# 14-I225-Main.net
KiCad netlist of a schematic drawn in Altium Designer
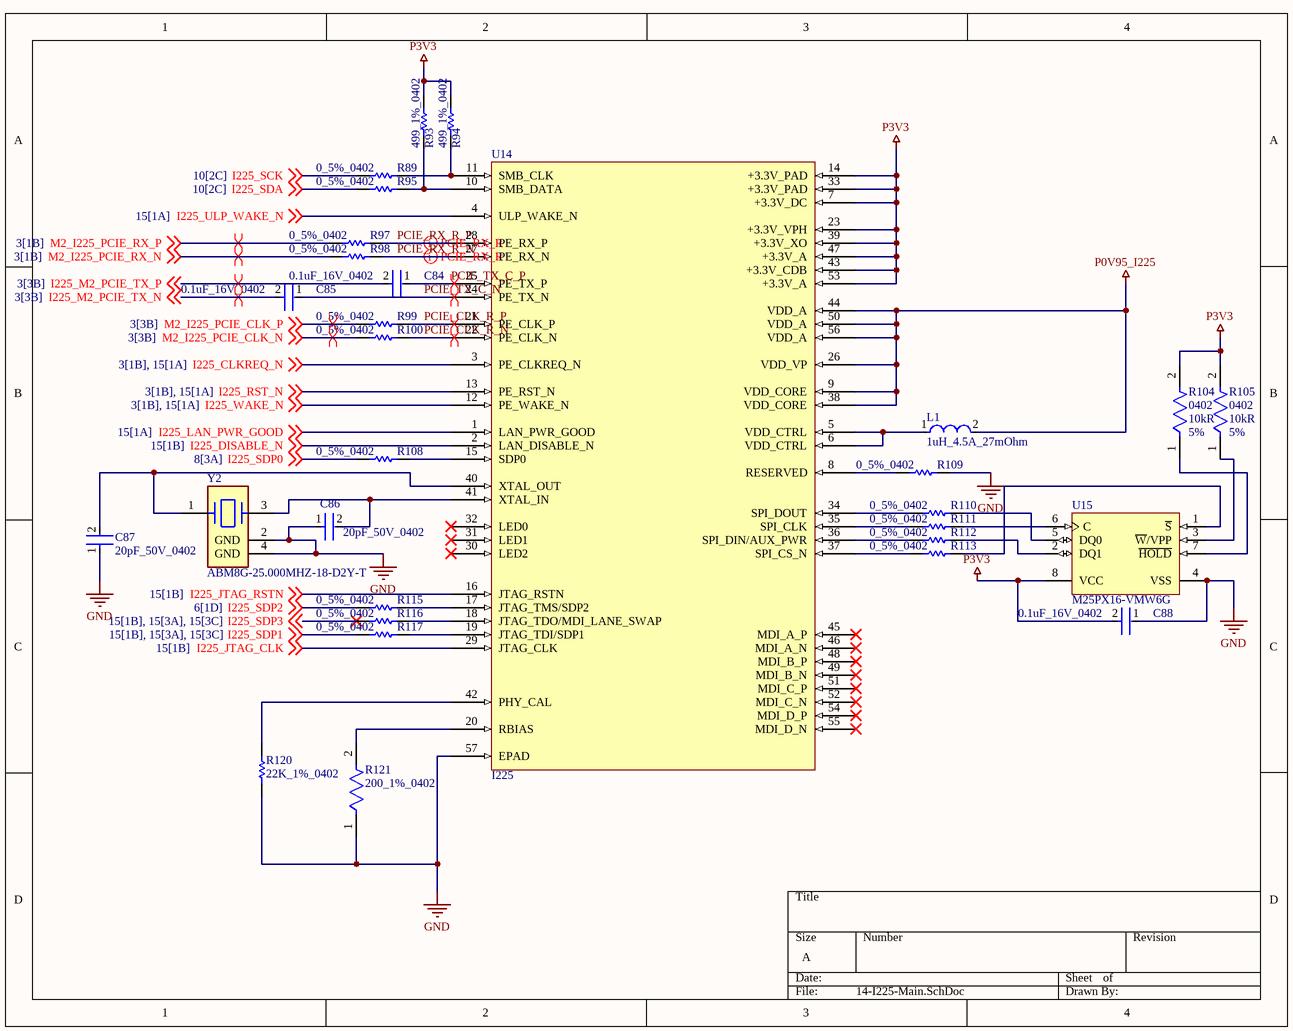
[diagram p0: 14-I225-Main.SchDoc]

(export (version "E")
  (design (tool "Eeschema 10.0.6"))
  (components
    (comp (ref "C84")
      (value "0.1uF_16V_0402")
      (footprint "FP-GRM15-MFG")
      (description "CAP CER 0.1UF 16V X7R 0402")
      (fields (field (name "MANUFACTURER PART NUMBER") "GRM155R71C104KA88D") (field (name "TOLERANCE") "10%"))
      (libsource (lib "Altium Content Vault") (part "236180d848d6139a670b325ea6854c9"))
    )
    (comp (ref "C85")
      (value "0.1uF_16V_0402")
      (footprint "FP-GRM15-MFG")
      (description "CAP CER 0.1UF 16V X7R 0402")
      (fields (field (name "MANUFACTURER PART NUMBER") "GRM155R71C104KA88D") (field (name "TOLERANCE") "10%"))
      (libsource (lib "Altium Content Vault") (part "236180d848d6139a670b325ea6854c9"))
    )
    (comp (ref "C86")
      (value "20pF_50V_0402")
      (footprint "FP-C0402-BB-MFG")
      (description "CAP CER 20PF 50V 5% NP0 0402")
      (fields
        (field (name "MANUFACTURER PART NUMBER") "C0402C200J5GACTU")
        (field (name "OCTOPART") "https://octopart.com/c0402c200j5gactu-kemet-9143900")
      )
      (libsource (lib "Altium Content Vault") (part "b4654b650e69147ec39a6b967a45e02"))
    )
    (comp (ref "C87")
      (value "20pF_50V_0402")
      (footprint "FP-C0402-BB-MFG")
      (description "CAP CER 20PF 50V 5% NP0 0402")
      (fields
        (field (name "MANUFACTURER PART NUMBER") "C0402C200J5GACTU")
        (field (name "OCTOPART") "https://octopart.com/c0402c200j5gactu-kemet-9143900")
      )
      (libsource (lib "Altium Content Vault") (part "b4654b650e69147ec39a6b967a45e02"))
    )
    (comp (ref "C88")
      (value "0.1uF_16V_0402")
      (footprint "FP-GRM15-MFG")
      (description "CAP CER 0.1UF 16V X7R 0402")
      (fields (field (name "MANUFACTURER PART NUMBER") "GRM155R71C104KA88D") (field (name "TOLERANCE") "10%"))
      (libsource (lib "Altium Content Vault") (part "236180d848d6139a670b325ea6854c9"))
    )
    (comp (ref "L1")
      (value "1uH_4.5A_27mOhm")
      (footprint "FP-IHLP-1616BZ-FP_1_8545x-MFG")
      (description "Fixed Inductors Commercial Low DCR Series SMT 1uH 4.5A 27mΩ 20%")
      (fields (field (name "TOLERANCE") "20%"))
      (libsource (lib "Altium Content Vault") (part "725321dda6339637d4d059423bc1c3c"))
    )
    (comp (ref "R89")
      (value "0_5%_0402")
      (footprint "RESC1005X40X25LL10T10")
      (fields (field (name "MANUFACTURER") "KOA Speer") (field (name "PART NUMBER") "RK73Z1ETTP"))
      (libsource (lib "Altium Content Vault") (part "RES"))
    )
    (comp (ref "R93")
      (value "499_1%_0402")
      (footprint "RESC1005X40X25LL05T05")
      (fields (field (name "MANUFACTURER") "Panasonic") (field (name "PART NUMBER") "ERJ-2RKF4990X"))
      (libsource (lib "Altium Content Vault") (part "RES"))
    )
    (comp (ref "R94")
      (value "499_1%_0402")
      (footprint "RESC1005X40X25LL05T05")
      (fields (field (name "MANUFACTURER") "Panasonic") (field (name "PART NUMBER") "ERJ-2RKF4990X"))
      (libsource (lib "Altium Content Vault") (part "RES"))
    )
    (comp (ref "R95")
      (value "0_5%_0402")
      (footprint "RESC1005X40X25LL10T10")
      (fields (field (name "MANUFACTURER") "KOA Speer") (field (name "PART NUMBER") "RK73Z1ETTP"))
      (libsource (lib "Altium Content Vault") (part "RES"))
    )
    (comp (ref "R97")
      (value "0_5%_0402")
      (footprint "RESC1005X40X25LL10T10")
      (fields (field (name "MANUFACTURER") "KOA Speer") (field (name "PART NUMBER") "RK73Z1ETTP"))
      (libsource (lib "Altium Content Vault") (part "RES"))
    )
    (comp (ref "R98")
      (value "0_5%_0402")
      (footprint "RESC1005X40X25LL10T10")
      (fields (field (name "MANUFACTURER") "KOA Speer") (field (name "PART NUMBER") "RK73Z1ETTP"))
      (libsource (lib "Altium Content Vault") (part "RES"))
    )
    (comp (ref "R99")
      (value "0_5%_0402")
      (footprint "RESC1005X40X25LL10T10")
      (fields (field (name "MANUFACTURER") "KOA Speer") (field (name "PART NUMBER") "RK73Z1ETTP"))
      (libsource (lib "Altium Content Vault") (part "RES"))
    )
    (comp (ref "R100")
      (value "0_5%_0402")
      (footprint "RESC1005X40X25LL10T10")
      (fields (field (name "MANUFACTURER") "KOA Speer") (field (name "PART NUMBER") "RK73Z1ETTP"))
      (libsource (lib "Altium Content Vault") (part "RES"))
    )
    (comp (ref "R104")
      (value "CRCW040210K0JNED")
      (footprint "FP-CRCW0402-e3-IPC_B")
      (description "RES Thick Film, 10kΩ, 5%, 0.063W, 200ppm/°C, 0402")
      (fields
        (field (name "CASE/PACKAGE") "0402")
        (field (name "RESISTANCE") "10kR")
        (field (name "TOLERANCE") "5%")
      )
      (libsource (lib "Altium Content Vault") (part "1029c3af85768c4190bb7ad29bc67b5"))
    )
    (comp (ref "R105")
      (value "CRCW040210K0JNED")
      (footprint "FP-CRCW0402-e3-IPC_B")
      (description "RES Thick Film, 10kΩ, 5%, 0.063W, 200ppm/°C, 0402")
      (fields
        (field (name "CASE/PACKAGE") "0402")
        (field (name "RESISTANCE") "10kR")
        (field (name "TOLERANCE") "5%")
      )
      (libsource (lib "Altium Content Vault") (part "1029c3af85768c4190bb7ad29bc67b5"))
    )
    (comp (ref "R108")
      (value "0_5%_0402")
      (footprint "RESC1005X40X25LL10T10")
      (fields (field (name "MANUFACTURER") "KOA Speer") (field (name "PART NUMBER") "RK73Z1ETTP"))
      (libsource (lib "Altium Content Vault") (part "RES"))
    )
    (comp (ref "R109")
      (value "0_5%_0402")
      (footprint "RESC1005X40X25LL10T10")
      (fields (field (name "MANUFACTURER") "KOA Speer") (field (name "PART NUMBER") "RK73Z1ETTP"))
      (libsource (lib "Altium Content Vault") (part "RES"))
    )
    (comp (ref "R110")
      (value "0_5%_0402")
      (footprint "RESC1005X40X25LL10T10")
      (fields (field (name "MANUFACTURER") "KOA Speer") (field (name "PART NUMBER") "RK73Z1ETTP"))
      (libsource (lib "Altium Content Vault") (part "RES"))
    )
    (comp (ref "R111")
      (value "0_5%_0402")
      (footprint "RESC1005X40X25LL10T10")
      (fields (field (name "MANUFACTURER") "KOA Speer") (field (name "PART NUMBER") "RK73Z1ETTP"))
      (libsource (lib "Altium Content Vault") (part "RES"))
    )
    (comp (ref "R112")
      (value "0_5%_0402")
      (footprint "RESC1005X40X25LL10T10")
      (fields (field (name "MANUFACTURER") "KOA Speer") (field (name "PART NUMBER") "RK73Z1ETTP"))
      (libsource (lib "Altium Content Vault") (part "RES"))
    )
    (comp (ref "R113")
      (value "0_5%_0402")
      (footprint "RESC1005X40X25LL10T10")
      (fields (field (name "MANUFACTURER") "KOA Speer") (field (name "PART NUMBER") "RK73Z1ETTP"))
      (libsource (lib "Altium Content Vault") (part "RES"))
    )
    (comp (ref "R115")
      (value "0_5%_0402")
      (footprint "RESC1005X40X25LL10T10")
      (fields (field (name "MANUFACTURER") "KOA Speer") (field (name "PART NUMBER") "RK73Z1ETTP"))
      (libsource (lib "Altium Content Vault") (part "RES"))
    )
    (comp (ref "R116")
      (value "0_5%_0402")
      (footprint "RESC1005X40X25LL10T10")
      (fields (field (name "MANUFACTURER") "KOA Speer") (field (name "PART NUMBER") "RK73Z1ETTP"))
      (libsource (lib "Altium Content Vault") (part "RES"))
    )
    (comp (ref "R117")
      (value "0_5%_0402")
      (footprint "RESC1005X40X25LL10T10")
      (fields (field (name "MANUFACTURER") "KOA Speer") (field (name "PART NUMBER") "RK73Z1ETTP"))
      (libsource (lib "Altium Content Vault") (part "RES"))
    )
    (comp (ref "R120")
      (value "22K_1%_0402")
      (footprint "RESC1005X40X25NL05T05")
      (fields (field (name "PART NUMBER") "CRCW040222K0FKED") (field (name "MANUFACTURER") "Vishay Dale"))
      (libsource (lib "Altium Content Vault") (part "RES"))
    )
    (comp (ref "R121")
      (value "200_1%_0402")
      (footprint "FP-CRCW0402-e3-IPC_C")
      (description "RES Thick Film, 200Ω, 1%, 0.063W, 100ppm/°C, 0402")
      (fields (field (name "TOLERANCE") "1%"))
      (libsource (lib "Altium Content Vault") (part "1029c3af85768c4190bb7ad29bc67b5"))
    )
    (comp (ref "U14") (value "I225") (footprint "I225 QFN56") (libsource (lib "TimeStick_Lib") (part "I225")))
    (comp (ref "U15")
      (value "M25PX16-VMW6G")
      (footprint "MICT-MW-8_N")
      (fields (field (name "VOLTAGE") "2.3V-3.6VÂ") (field (name "MANUFACTURER") "Micron"))
      (libsource (lib "Altium Content Vault") (part "MICT-M25PX16-VMW-8"))
    )
    (comp (ref "Y2")
      (value "ABM8G-25.000MHZ-18-D2Y-T")
      (footprint "FP-ABM8G-MFG")
      (description "CRYSTAL 25.0000MHZ 18PF SMD")
      (fields
        (field (name "MANUFACTURER") "Abracon")
        (field (name "OCTOPART") "https://octopart.com/abm8g-25.000mhz-18-d2y-t-abracon-12676602")
      )
      (libsource (lib "Altium Content Vault") (part "82af6c543cb7a88a4cbd02a3a01c293"))
    )
  )
  (nets
    (net (code "1") (name "/PCIE_CLK_R_N") (class "Default")
      (node (ref "R100") (pin "2") (pinfunction "2_2") (pintype "passive"))
      (node (ref "U14") (pin "22") (pinfunction "PE_CLK_N_22") (pintype "input"))
    )
    (net (code "2") (name "/PCIE_CLK_R_P") (class "Default")
      (node (ref "R99") (pin "2") (pinfunction "2_2") (pintype "passive"))
      (node (ref "U14") (pin "21") (pinfunction "PE_CLK_P_21") (pintype "input"))
    )
    (net (code "3") (name "/PCIE_RX_R_N") (class "Default")
      (node (ref "R98") (pin "2") (pinfunction "2_2") (pintype "passive"))
      (node (ref "U14") (pin "27") (pinfunction "PE_RX_N_27") (pintype "input"))
    )
    (net (code "4") (name "/PCIE_RX_R_P") (class "Default")
      (node (ref "R97") (pin "2") (pinfunction "2_2") (pintype "passive"))
      (node (ref "U14") (pin "28") (pinfunction "PE_RX_P_28") (pintype "input"))
    )
    (net (code "5") (name "/PCIE_TX_C_N") (class "Default")
      (node (ref "C85") (pin "1") (pinfunction "1_1") (pintype "passive"))
      (node (ref "U14") (pin "24") (pinfunction "PE_TX_N_24") (pintype "input"))
    )
    (net (code "6") (name "/PCIE_TX_C_P") (class "Default")
      (node (ref "C84") (pin "1") (pinfunction "1_1") (pintype "passive"))
      (node (ref "U14") (pin "25") (pinfunction "PE_TX_P_25") (pintype "input"))
    )
    (net (code "7") (name "GND") (class "Default")
      (node (ref "C86") (pin "1") (pinfunction "1_1") (pintype "passive"))
      (node (ref "C87") (pin "1") (pinfunction "1_1") (pintype "passive"))
      (node (ref "C88") (pin "1") (pinfunction "1_1") (pintype "passive"))
      (node (ref "R109") (pin "2") (pinfunction "2_2") (pintype "passive"))
      (node (ref "R120") (pin "1") (pinfunction "1_1") (pintype "passive"))
      (node (ref "R121") (pin "1") (pinfunction "1_1") (pintype "passive"))
      (node (ref "U14") (pin "57") (pinfunction "EPAD_57") (pintype "input"))
      (node (ref "U15") (pin "4") (pinfunction "VSS_4") (pintype "power_in"))
      (node (ref "Y2") (pin "2") (pinfunction "GND_2") (pintype "power_in"))
      (node (ref "Y2") (pin "4") (pinfunction "GND_4") (pintype "power_in"))
    )
    (net (code "8") (name "I225_CLKREQ_N") (class "Default")
      (node (ref "U14") (pin "3") (pinfunction "PE_CLKREQ_N_3") (pintype "input"))
    )
    (net (code "9") (name "I225_DISABLE_N") (class "Default")
      (node (ref "U14") (pin "2") (pinfunction "LAN_DISABLE_N_2") (pintype "input"))
    )
    (net (code "10") (name "I225_JTAG_CLK") (class "Default")
      (node (ref "U14") (pin "29") (pinfunction "JTAG_CLK_29") (pintype "input"))
    )
    (net (code "11") (name "I225_JTAG_RSTN") (class "Default")
      (node (ref "U14") (pin "16") (pinfunction "JTAG_RSTN_16") (pintype "input"))
    )
    (net (code "12") (name "I225_LAN_PWR_GOOD") (class "Default")
      (node (ref "U14") (pin "1") (pinfunction "LAN_PWR_GOOD_1") (pintype "input"))
    )
    (net (code "13") (name "I225_M2_PCIE_TX_N") (class "Default")
      (node (ref "C85") (pin "2") (pinfunction "2_2") (pintype "passive"))
    )
    (net (code "14") (name "I225_M2_PCIE_TX_P") (class "Default")
      (node (ref "C84") (pin "2") (pinfunction "2_2") (pintype "passive"))
    )
    (net (code "15") (name "I225_RST_N") (class "Default")
      (node (ref "U14") (pin "13") (pinfunction "PE_RST_N_13") (pintype "input"))
    )
    (net (code "16") (name "I225_SCK") (class "Default")
      (node (ref "R89") (pin "1") (pinfunction "1_1") (pintype "passive"))
    )
    (net (code "17") (name "I225_SDA") (class "Default")
      (node (ref "R95") (pin "1") (pinfunction "1_1") (pintype "passive"))
    )
    (net (code "18") (name "I225_SDP0") (class "Default")
      (node (ref "R108") (pin "1") (pinfunction "1_1") (pintype "passive"))
    )
    (net (code "19") (name "I225_SDP1") (class "Default")
      (node (ref "R117") (pin "1") (pinfunction "1_1") (pintype "passive"))
    )
    (net (code "20") (name "I225_SDP2") (class "Default")
      (node (ref "R115") (pin "1") (pinfunction "1_1") (pintype "passive"))
    )
    (net (code "21") (name "I225_SDP3") (class "Default")
      (node (ref "R116") (pin "1") (pinfunction "1_1") (pintype "passive"))
    )
    (net (code "22") (name "I225_ULP_WAKE_N") (class "Default")
      (node (ref "U14") (pin "4") (pinfunction "ULP_WAKE_N_4") (pintype "input"))
    )
    (net (code "23") (name "I225_WAKE_N") (class "Default")
      (node (ref "U14") (pin "12") (pinfunction "PE_WAKE_N_12") (pintype "input"))
    )
    (net (code "24") (name "M2_I225_PCIE_CLK_N") (class "Default")
      (node (ref "R100") (pin "1") (pinfunction "1_1") (pintype "passive"))
    )
    (net (code "25") (name "M2_I225_PCIE_CLK_P") (class "Default")
      (node (ref "R99") (pin "1") (pinfunction "1_1") (pintype "passive"))
    )
    (net (code "26") (name "M2_I225_PCIE_RX_N") (class "Default")
      (node (ref "R98") (pin "1") (pinfunction "1_1") (pintype "passive"))
    )
    (net (code "27") (name "M2_I225_PCIE_RX_P") (class "Default")
      (node (ref "R97") (pin "1") (pinfunction "1_1") (pintype "passive"))
    )
    (net (code "28") (name "Net-(L1-Pad1)") (class "Default")
      (node (ref "L1") (pin "1") (pinfunction "1_1") (pintype "passive"))
      (node (ref "U14") (pin "5") (pinfunction "VDD_CTRL_5") (pintype "input"))
      (node (ref "U14") (pin "6") (pinfunction "VDD_CTRL_6") (pintype "input"))
    )
    (net (code "29") (name "Net-(U14-JTAG_TDI{slash}SDP1)") (class "Default")
      (node (ref "R117") (pin "2") (pinfunction "2_2") (pintype "passive"))
      (node (ref "U14") (pin "19") (pinfunction "JTAG_TDI/SDP1_19") (pintype "input"))
    )
    (net (code "30") (name "Net-(U14-JTAG_TDO{slash}MDI_LANE_SWAP)") (class "Default")
      (node (ref "R116") (pin "2") (pinfunction "2_2") (pintype "passive"))
      (node (ref "U14") (pin "18") (pinfunction "JTAG_TDO/MDI_LANE_SWAP_18") (pintype "input"))
    )
    (net (code "31") (name "Net-(U14-JTAG_TMS{slash}SDP2)") (class "Default")
      (node (ref "R115") (pin "2") (pinfunction "2_2") (pintype "passive"))
      (node (ref "U14") (pin "17") (pinfunction "JTAG_TMS/SDP2_17") (pintype "input"))
    )
    (net (code "32") (name "Net-(U14-PHY_CAL)") (class "Default")
      (node (ref "R120") (pin "2") (pinfunction "2_2") (pintype "passive"))
      (node (ref "U14") (pin "42") (pinfunction "PHY_CAL_42") (pintype "input"))
    )
    (net (code "33") (name "Net-(U14-RBIAS)") (class "Default")
      (node (ref "R121") (pin "2") (pinfunction "2_2") (pintype "passive"))
      (node (ref "U14") (pin "20") (pinfunction "RBIAS_20") (pintype "input"))
    )
    (net (code "34") (name "Net-(U14-RESERVED)") (class "Default")
      (node (ref "R109") (pin "1") (pinfunction "1_1") (pintype "passive"))
      (node (ref "U14") (pin "8") (pinfunction "RESERVED_8") (pintype "input"))
    )
    (net (code "35") (name "Net-(U14-SDP0)") (class "Default")
      (node (ref "R108") (pin "2") (pinfunction "2_2") (pintype "passive"))
      (node (ref "U14") (pin "15") (pinfunction "SDP0_15") (pintype "input"))
    )
    (net (code "36") (name "Net-(U14-SMB_CLK)") (class "Default")
      (node (ref "R89") (pin "2") (pinfunction "2_2") (pintype "passive"))
      (node (ref "R94") (pin "1") (pinfunction "1_1") (pintype "passive"))
      (node (ref "U14") (pin "11") (pinfunction "SMB_CLK_11") (pintype "input"))
    )
    (net (code "37") (name "Net-(U14-SMB_DATA)") (class "Default")
      (node (ref "R93") (pin "1") (pinfunction "1_1") (pintype "passive"))
      (node (ref "R95") (pin "2") (pinfunction "2_2") (pintype "passive"))
      (node (ref "U14") (pin "10") (pinfunction "SMB_DATA_10") (pintype "input"))
    )
    (net (code "38") (name "Net-(U14-SPI_CLK)") (class "Default")
      (node (ref "R111") (pin "1") (pinfunction "1_1") (pintype "passive"))
      (node (ref "U14") (pin "35") (pinfunction "SPI_CLK_35") (pintype "input"))
    )
    (net (code "39") (name "Net-(U14-SPI_CS_N)") (class "Default")
      (node (ref "R113") (pin "1") (pinfunction "1_1") (pintype "passive"))
      (node (ref "U14") (pin "37") (pinfunction "SPI_CS_N_37") (pintype "input"))
    )
    (net (code "40") (name "Net-(U14-SPI_DIN{slash}AUX_PWR)") (class "Default")
      (node (ref "R112") (pin "1") (pinfunction "1_1") (pintype "passive"))
      (node (ref "U14") (pin "36") (pinfunction "SPI_DIN/AUX_PWR_36") (pintype "input"))
    )
    (net (code "41") (name "Net-(U14-SPI_DOUT)") (class "Default")
      (node (ref "R110") (pin "1") (pinfunction "1_1") (pintype "passive"))
      (node (ref "U14") (pin "34") (pinfunction "SPI_DOUT_34") (pintype "input"))
    )
    (net (code "42") (name "Net-(U14-XTAL_IN)") (class "Default")
      (node (ref "C86") (pin "2") (pinfunction "2_2") (pintype "passive"))
      (node (ref "U14") (pin "41") (pinfunction "XTAL_IN_41") (pintype "input"))
      (node (ref "Y2") (pin "3") (pinfunction "3_3") (pintype "passive"))
    )
    (net (code "43") (name "Net-(U14-XTAL_OUT)") (class "Default")
      (node (ref "C87") (pin "2") (pinfunction "2_2") (pintype "passive"))
      (node (ref "U14") (pin "40") (pinfunction "XTAL_OUT_40") (pintype "input"))
      (node (ref "Y2") (pin "1") (pinfunction "1_1") (pintype "passive"))
    )
    (net (code "44") (name "Net-(U15-C)") (class "Default")
      (node (ref "R111") (pin "2") (pinfunction "2_2") (pintype "passive"))
      (node (ref "U15") (pin "6") (pinfunction "C_6") (pintype "input"))
    )
    (net (code "45") (name "Net-(U15-DQ0)") (class "Default")
      (node (ref "R110") (pin "2") (pinfunction "2_2") (pintype "passive"))
      (node (ref "U15") (pin "5") (pinfunction "DQ0_5") (pintype "bidirectional"))
    )
    (net (code "46") (name "Net-(U15-DQ1)") (class "Default")
      (node (ref "R112") (pin "2") (pinfunction "2_2") (pintype "passive"))
      (node (ref "U15") (pin "2") (pinfunction "DQ1_2") (pintype "bidirectional"))
    )
    (net (code "47") (name "Net-(U15-~{HOLD})") (class "Default")
      (node (ref "R104") (pin "1") (pinfunction "1_1") (pintype "passive"))
      (node (ref "U15") (pin "7") (pinfunction "~{HOLD}_7") (pintype "input"))
    )
    (net (code "48") (name "Net-(U15-~{S})") (class "Default")
      (node (ref "R113") (pin "2") (pinfunction "2_2") (pintype "passive"))
      (node (ref "U15") (pin "1") (pinfunction "~{S}_1") (pintype "input"))
    )
    (net (code "49") (name "Net-(U15-~{W}{slash}VPP)") (class "Default")
      (node (ref "R105") (pin "1") (pinfunction "1_1") (pintype "passive"))
      (node (ref "U15") (pin "3") (pinfunction "~{W}/VPP_3") (pintype "input"))
    )
    (net (code "50") (name "P0V95_I225") (class "Default")
      (node (ref "L1") (pin "2") (pinfunction "2_2") (pintype "passive"))
      (node (ref "U14") (pin "26") (pinfunction "VDD_VP_26") (pintype "input"))
      (node (ref "U14") (pin "38") (pinfunction "VDD_CORE_38") (pintype "input"))
      (node (ref "U14") (pin "44") (pinfunction "VDD_A_44") (pintype "input"))
      (node (ref "U14") (pin "50") (pinfunction "VDD_A_50") (pintype "input"))
      (node (ref "U14") (pin "56") (pinfunction "VDD_A_56") (pintype "input"))
      (node (ref "U14") (pin "9") (pinfunction "VDD_CORE_9") (pintype "input"))
    )
    (net (code "51") (name "P3V3") (class "Default")
      (node (ref "C88") (pin "2") (pinfunction "2_2") (pintype "passive"))
      (node (ref "R104") (pin "2") (pinfunction "2_2") (pintype "passive"))
      (node (ref "R105") (pin "2") (pinfunction "2_2") (pintype "passive"))
      (node (ref "R93") (pin "2") (pinfunction "2_2") (pintype "passive"))
      (node (ref "R94") (pin "2") (pinfunction "2_2") (pintype "passive"))
      (node (ref "U14") (pin "14") (pinfunction "+3.3V_PAD_14") (pintype "input"))
      (node (ref "U14") (pin "23") (pinfunction "+3.3V_VPH_23") (pintype "input"))
      (node (ref "U14") (pin "33") (pinfunction "+3.3V_PAD_33") (pintype "input"))
      (node (ref "U14") (pin "39") (pinfunction "+3.3V_XO_39") (pintype "input"))
      (node (ref "U14") (pin "43") (pinfunction "+3.3V_CDB_43") (pintype "input"))
      (node (ref "U14") (pin "47") (pinfunction "+3.3V_A_47") (pintype "input"))
      (node (ref "U14") (pin "53") (pinfunction "+3.3V_A_53") (pintype "input"))
      (node (ref "U14") (pin "7") (pinfunction "+3.3V_DC_7") (pintype "input"))
      (node (ref "U15") (pin "8") (pinfunction "VCC_8") (pintype "power_in"))
    )
    (net (code "52") (name "unconnected-(U14-LED0-Pad32)") (class "Default")
      (node (ref "U14") (pin "32") (pinfunction "LED0_32") (pintype "input+no_connect"))
    )
    (net (code "53") (name "unconnected-(U14-LED1-Pad31)") (class "Default")
      (node (ref "U14") (pin "31") (pinfunction "LED1_31") (pintype "input+no_connect"))
    )
    (net (code "54") (name "unconnected-(U14-LED2-Pad30)") (class "Default")
      (node (ref "U14") (pin "30") (pinfunction "LED2_30") (pintype "input+no_connect"))
    )
    (net (code "55") (name "unconnected-(U14-MDI_A_N-Pad46)") (class "Default")
      (node (ref "U14") (pin "46") (pinfunction "MDI_A_N_46") (pintype "input+no_connect"))
    )
    (net (code "56") (name "unconnected-(U14-MDI_A_P-Pad45)") (class "Default")
      (node (ref "U14") (pin "45") (pinfunction "MDI_A_P_45") (pintype "input+no_connect"))
    )
    (net (code "57") (name "unconnected-(U14-MDI_B_N-Pad49)") (class "Default")
      (node (ref "U14") (pin "49") (pinfunction "MDI_B_N_49") (pintype "input+no_connect"))
    )
    (net (code "58") (name "unconnected-(U14-MDI_B_P-Pad48)") (class "Default")
      (node (ref "U14") (pin "48") (pinfunction "MDI_B_P_48") (pintype "input+no_connect"))
    )
    (net (code "59") (name "unconnected-(U14-MDI_C_N-Pad52)") (class "Default")
      (node (ref "U14") (pin "52") (pinfunction "MDI_C_N_52") (pintype "input+no_connect"))
    )
    (net (code "60") (name "unconnected-(U14-MDI_C_P-Pad51)") (class "Default")
      (node (ref "U14") (pin "51") (pinfunction "MDI_C_P_51") (pintype "input+no_connect"))
    )
    (net (code "61") (name "unconnected-(U14-MDI_D_N-Pad55)") (class "Default")
      (node (ref "U14") (pin "55") (pinfunction "MDI_D_N_55") (pintype "input+no_connect"))
    )
    (net (code "62") (name "unconnected-(U14-MDI_D_P-Pad54)") (class "Default")
      (node (ref "U14") (pin "54") (pinfunction "MDI_D_P_54") (pintype "input+no_connect"))
    )
  )
)
